# ts2068Interface.net
KiCad netlist of a schematic drawn in Altium Designer
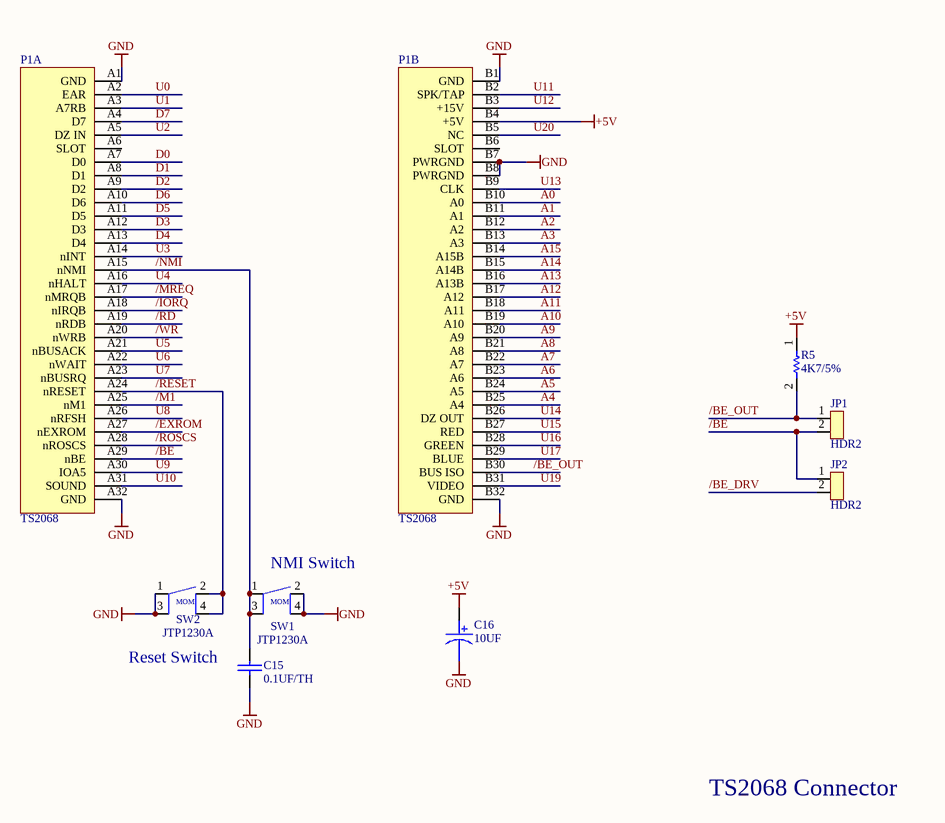
[diagram p0: ts2068Interface.SchDoc]

(export (version "E")
  (design (tool "Eeschema 10.0.6"))
  (components
    (comp (ref "C15")
      (value "0.1UF/TH")
      (footprint "CAPH5")
      (description "0.1 µF ±10% 50V Ceramic Capacitor X7R Radial")
      (fields (field (name "MFG") "Vishay"))
      (libsource (lib "CapacitorsTH") (part "0.1UF/TH"))
    )
    (comp (ref "C16")
      (value "10UF")
      (footprint "CAP10EL")
      (description "CAP ALUM 10UF 20% 16V RADIAL")
      (fields (field (name "MFG") "Panasonic"))
      (libsource (lib "CapacitorsTH") (part "10UF"))
    )
    (comp (ref "JP1") (value "HDR2") (footprint "HDR2") (libsource (lib "Connectors") (part "HDR2")))
    (comp (ref "JP2") (value "HDR2") (footprint "HDR2") (libsource (lib "Connectors") (part "HDR2")))
    (comp (ref "P1") (value "TS2068") (footprint "TS2068A") (libsource (lib "Modules") (part "TS2068")))
    (comp (ref "R5")
      (value "4K7/5%")
      (footprint "CF18")
      (description "RES 4.7K OHM 5% 1/8W AXIAL")
      (fields (field (name "MFG") "Stackpole"))
      (libsource (lib "ResistorsTH") (part "4K7/5%"))
    )
    (comp (ref "SW1")
      (value "JTP1230A")
      (footprint "TACSW_6.5x4.5")
      (description "Tactile Switch SPST-NO Top Actuated Through Hole")
      (fields (field (name "MFG") "Apem"))
      (libsource (lib "Misc") (part "JTP1230A"))
    )
    (comp (ref "SW2")
      (value "JTP1230A")
      (footprint "TACSW_6.5x4.5")
      (description "Tactile Switch SPST-NO Top Actuated Through Hole")
      (fields (field (name "MFG") "Apem"))
      (libsource (lib "Misc") (part "JTP1230A"))
    )
  )
  (nets
    (net (code "1") (name "+5V") (class "Default")
      (node (ref "C16") (pin "1") (pinfunction "1_1") (pintype "passive"))
      (node (ref "P1") (pin "B4") (pinfunction "+5V_B4") (pintype "passive"))
      (node (ref "R5") (pin "1") (pinfunction "1_1") (pintype "passive"))
    )
    (net (code "2") (name "/A0") (class "Default")
      (node (ref "P1") (pin "B10") (pinfunction "A0_B10") (pintype "passive"))
    )
    (net (code "3") (name "/A1") (class "Default")
      (node (ref "P1") (pin "B11") (pinfunction "A1_B11") (pintype "passive"))
    )
    (net (code "4") (name "/A2") (class "Default")
      (node (ref "P1") (pin "B12") (pinfunction "A2_B12") (pintype "passive"))
    )
    (net (code "5") (name "/A3") (class "Default")
      (node (ref "P1") (pin "B13") (pinfunction "A3_B13") (pintype "passive"))
    )
    (net (code "6") (name "/A4") (class "Default")
      (node (ref "P1") (pin "B25") (pinfunction "A4_B25") (pintype "passive"))
    )
    (net (code "7") (name "/A5") (class "Default")
      (node (ref "P1") (pin "B24") (pinfunction "A5_B24") (pintype "passive"))
    )
    (net (code "8") (name "/A6") (class "Default")
      (node (ref "P1") (pin "B23") (pinfunction "A6_B23") (pintype "passive"))
    )
    (net (code "9") (name "/A7") (class "Default")
      (node (ref "P1") (pin "B22") (pinfunction "A7_B22") (pintype "passive"))
    )
    (net (code "10") (name "/A8") (class "Default")
      (node (ref "P1") (pin "B21") (pinfunction "A8_B21") (pintype "passive"))
    )
    (net (code "11") (name "/A9") (class "Default")
      (node (ref "P1") (pin "B20") (pinfunction "A9_B20") (pintype "passive"))
    )
    (net (code "12") (name "/A10") (class "Default")
      (node (ref "P1") (pin "B19") (pinfunction "A10_B19") (pintype "passive"))
    )
    (net (code "13") (name "/A11") (class "Default")
      (node (ref "P1") (pin "B18") (pinfunction "A11_B18") (pintype "passive"))
    )
    (net (code "14") (name "/A12") (class "Default")
      (node (ref "P1") (pin "B17") (pinfunction "A12_B17") (pintype "passive"))
    )
    (net (code "15") (name "/A13") (class "Default")
      (node (ref "P1") (pin "B16") (pinfunction "A13B_B16") (pintype "passive"))
    )
    (net (code "16") (name "/A14") (class "Default")
      (node (ref "P1") (pin "B15") (pinfunction "A14B_B15") (pintype "passive"))
    )
    (net (code "17") (name "/A15") (class "Default")
      (node (ref "P1") (pin "B14") (pinfunction "A15B_B14") (pintype "passive"))
    )
    (net (code "18") (name "/D0") (class "Default")
      (node (ref "P1") (pin "A7") (pinfunction "D0_A7") (pintype "passive"))
    )
    (net (code "19") (name "/D1") (class "Default")
      (node (ref "P1") (pin "A8") (pinfunction "D1_A8") (pintype "passive"))
    )
    (net (code "20") (name "/D2") (class "Default")
      (node (ref "P1") (pin "A9") (pinfunction "D2_A9") (pintype "passive"))
    )
    (net (code "21") (name "/D3") (class "Default")
      (node (ref "P1") (pin "A12") (pinfunction "D3_A12") (pintype "passive"))
    )
    (net (code "22") (name "/D4") (class "Default")
      (node (ref "P1") (pin "A13") (pinfunction "D4_A13") (pintype "passive"))
    )
    (net (code "23") (name "/D5") (class "Default")
      (node (ref "P1") (pin "A11") (pinfunction "D5_A11") (pintype "passive"))
    )
    (net (code "24") (name "/D6") (class "Default")
      (node (ref "P1") (pin "A10") (pinfunction "D6_A10") (pintype "passive"))
    )
    (net (code "25") (name "/D7") (class "Default")
      (node (ref "P1") (pin "A4") (pinfunction "D7_A4") (pintype "passive"))
    )
    (net (code "26") (name "/U0") (class "Default")
      (node (ref "P1") (pin "A2") (pinfunction "EAR_A2") (pintype "passive"))
    )
    (net (code "27") (name "/U1") (class "Default")
      (node (ref "P1") (pin "A3") (pinfunction "A7RB_A3") (pintype "passive"))
    )
    (net (code "28") (name "/U2") (class "Default")
      (node (ref "P1") (pin "A5") (pinfunction "DZ_IN_A5") (pintype "passive"))
    )
    (net (code "29") (name "/U3") (class "Default")
      (node (ref "P1") (pin "A14") (pinfunction "nINT_A14") (pintype "passive"))
    )
    (net (code "30") (name "/U4") (class "Default")
      (node (ref "P1") (pin "A16") (pinfunction "nHALT_A16") (pintype "passive"))
    )
    (net (code "31") (name "/U5") (class "Default")
      (node (ref "P1") (pin "A21") (pinfunction "nBUSACK_A21") (pintype "passive"))
    )
    (net (code "32") (name "/U6") (class "Default")
      (node (ref "P1") (pin "A22") (pinfunction "nWAIT_A22") (pintype "passive"))
    )
    (net (code "33") (name "/U7") (class "Default")
      (node (ref "P1") (pin "A23") (pinfunction "nBUSRQ_A23") (pintype "passive"))
    )
    (net (code "34") (name "/U8") (class "Default")
      (node (ref "P1") (pin "A26") (pinfunction "nRFSH_A26") (pintype "passive"))
    )
    (net (code "35") (name "/U9") (class "Default")
      (node (ref "P1") (pin "A30") (pinfunction "IOA5_A30") (pintype "passive"))
    )
    (net (code "36") (name "/U10") (class "Default")
      (node (ref "P1") (pin "A31") (pinfunction "SOUND_A31") (pintype "passive"))
    )
    (net (code "37") (name "/U11") (class "Default")
      (node (ref "P1") (pin "B2") (pinfunction "SPK/TAP_B2") (pintype "passive"))
    )
    (net (code "38") (name "/U12") (class "Default")
      (node (ref "P1") (pin "B3") (pinfunction "+15V_B3") (pintype "passive"))
    )
    (net (code "39") (name "/U13") (class "Default")
      (node (ref "P1") (pin "B9") (pinfunction "CLK_B9") (pintype "passive"))
    )
    (net (code "40") (name "/U14") (class "Default")
      (node (ref "P1") (pin "B26") (pinfunction "DZ_OUT_B26") (pintype "passive"))
    )
    (net (code "41") (name "/U15") (class "Default")
      (node (ref "P1") (pin "B27") (pinfunction "RED_B27") (pintype "passive"))
    )
    (net (code "42") (name "/U16") (class "Default")
      (node (ref "P1") (pin "B28") (pinfunction "GREEN_B28") (pintype "passive"))
    )
    (net (code "43") (name "/U17") (class "Default")
      (node (ref "P1") (pin "B29") (pinfunction "BLUE_B29") (pintype "passive"))
    )
    (net (code "44") (name "/U19") (class "Default")
      (node (ref "P1") (pin "B31") (pinfunction "VIDEO_B31") (pintype "passive"))
    )
    (net (code "45") (name "/U20") (class "Default")
      (node (ref "P1") (pin "B5") (pinfunction "NC_B5") (pintype "passive"))
    )
    (net (code "46") (name "/{slash}BE") (class "Default")
      (node (ref "JP1") (pin "2") (pintype "passive"))
      (node (ref "JP2") (pin "1") (pintype "passive"))
      (node (ref "P1") (pin "A29") (pinfunction "nBE_A29") (pintype "passive"))
    )
    (net (code "47") (name "/{slash}BE_DRV") (class "Default")
      (node (ref "JP2") (pin "2") (pintype "passive"))
    )
    (net (code "48") (name "/{slash}BE_OUT") (class "Default")
      (node (ref "JP1") (pin "1") (pintype "passive"))
      (node (ref "P1") (pin "B30") (pinfunction "BUS_ISO_B30") (pintype "passive"))
      (node (ref "R5") (pin "2") (pinfunction "2_2") (pintype "passive"))
    )
    (net (code "49") (name "/{slash}EXROM") (class "Default")
      (node (ref "P1") (pin "A27") (pinfunction "nEXROM_A27") (pintype "passive"))
    )
    (net (code "50") (name "/{slash}IORQ") (class "Default")
      (node (ref "P1") (pin "A18") (pinfunction "nIRQB_A18") (pintype "passive"))
    )
    (net (code "51") (name "/{slash}M1") (class "Default")
      (node (ref "P1") (pin "A25") (pinfunction "nM1_A25") (pintype "passive"))
    )
    (net (code "52") (name "/{slash}MREQ") (class "Default")
      (node (ref "P1") (pin "A17") (pinfunction "nMRQB_A17") (pintype "passive"))
    )
    (net (code "53") (name "/{slash}NMI") (class "Default")
      (node (ref "C15") (pin "2") (pintype "passive"))
      (node (ref "P1") (pin "A15") (pinfunction "nNMI_A15") (pintype "passive"))
      (node (ref "SW1") (pin "1") (pinfunction "1_1") (pintype "passive"))
      (node (ref "SW1") (pin "3") (pintype "passive"))
    )
    (net (code "54") (name "/{slash}RD") (class "Default")
      (node (ref "P1") (pin "A19") (pinfunction "nRDB_A19") (pintype "passive"))
    )
    (net (code "55") (name "/{slash}RESET") (class "Default")
      (node (ref "P1") (pin "A24") (pinfunction "nRESET_A24") (pintype "passive"))
      (node (ref "SW2") (pin "2") (pinfunction "2_2") (pintype "passive"))
      (node (ref "SW2") (pin "4") (pinfunction "2_4") (pintype "passive"))
    )
    (net (code "56") (name "/{slash}ROSCS") (class "Default")
      (node (ref "P1") (pin "A28") (pinfunction "nROSCS_A28") (pintype "passive"))
    )
    (net (code "57") (name "/{slash}WR") (class "Default")
      (node (ref "P1") (pin "A20") (pinfunction "nWRB_A20") (pintype "passive"))
    )
    (net (code "58") (name "GND") (class "Default")
      (node (ref "C15") (pin "1") (pintype "passive"))
      (node (ref "C16") (pin "2") (pinfunction "2_2") (pintype "passive"))
      (node (ref "P1") (pin "A1") (pinfunction "GND_A1") (pintype "passive"))
      (node (ref "P1") (pin "A32") (pinfunction "GND_A32") (pintype "passive"))
      (node (ref "P1") (pin "B1") (pinfunction "GND_B1") (pintype "passive"))
      (node (ref "P1") (pin "B32") (pinfunction "GND_B32") (pintype "passive"))
      (node (ref "P1") (pin "B7") (pinfunction "PWRGND_B7") (pintype "passive"))
      (node (ref "P1") (pin "B8") (pinfunction "PWRGND_B8") (pintype "passive"))
      (node (ref "SW1") (pin "2") (pinfunction "2_2") (pintype "passive"))
      (node (ref "SW1") (pin "4") (pinfunction "2_4") (pintype "passive"))
      (node (ref "SW2") (pin "1") (pinfunction "1_1") (pintype "passive"))
      (node (ref "SW2") (pin "3") (pintype "passive"))
    )
    (net (code "59") (name "unconnected-(P1A-SLOT-PadA6)") (class "Default")
      (node (ref "P1") (pin "A6") (pinfunction "SLOT_A6") (pintype "passive"))
    )
    (net (code "60") (name "unconnected-(P1B-SLOT-PadB6)") (class "Default")
      (node (ref "P1") (pin "B6") (pinfunction "SLOT_B6") (pintype "passive"))
    )
  )
)
